# Anand1-BottomNew.net
KiCad netlist of a schematic drawn in EAGLE
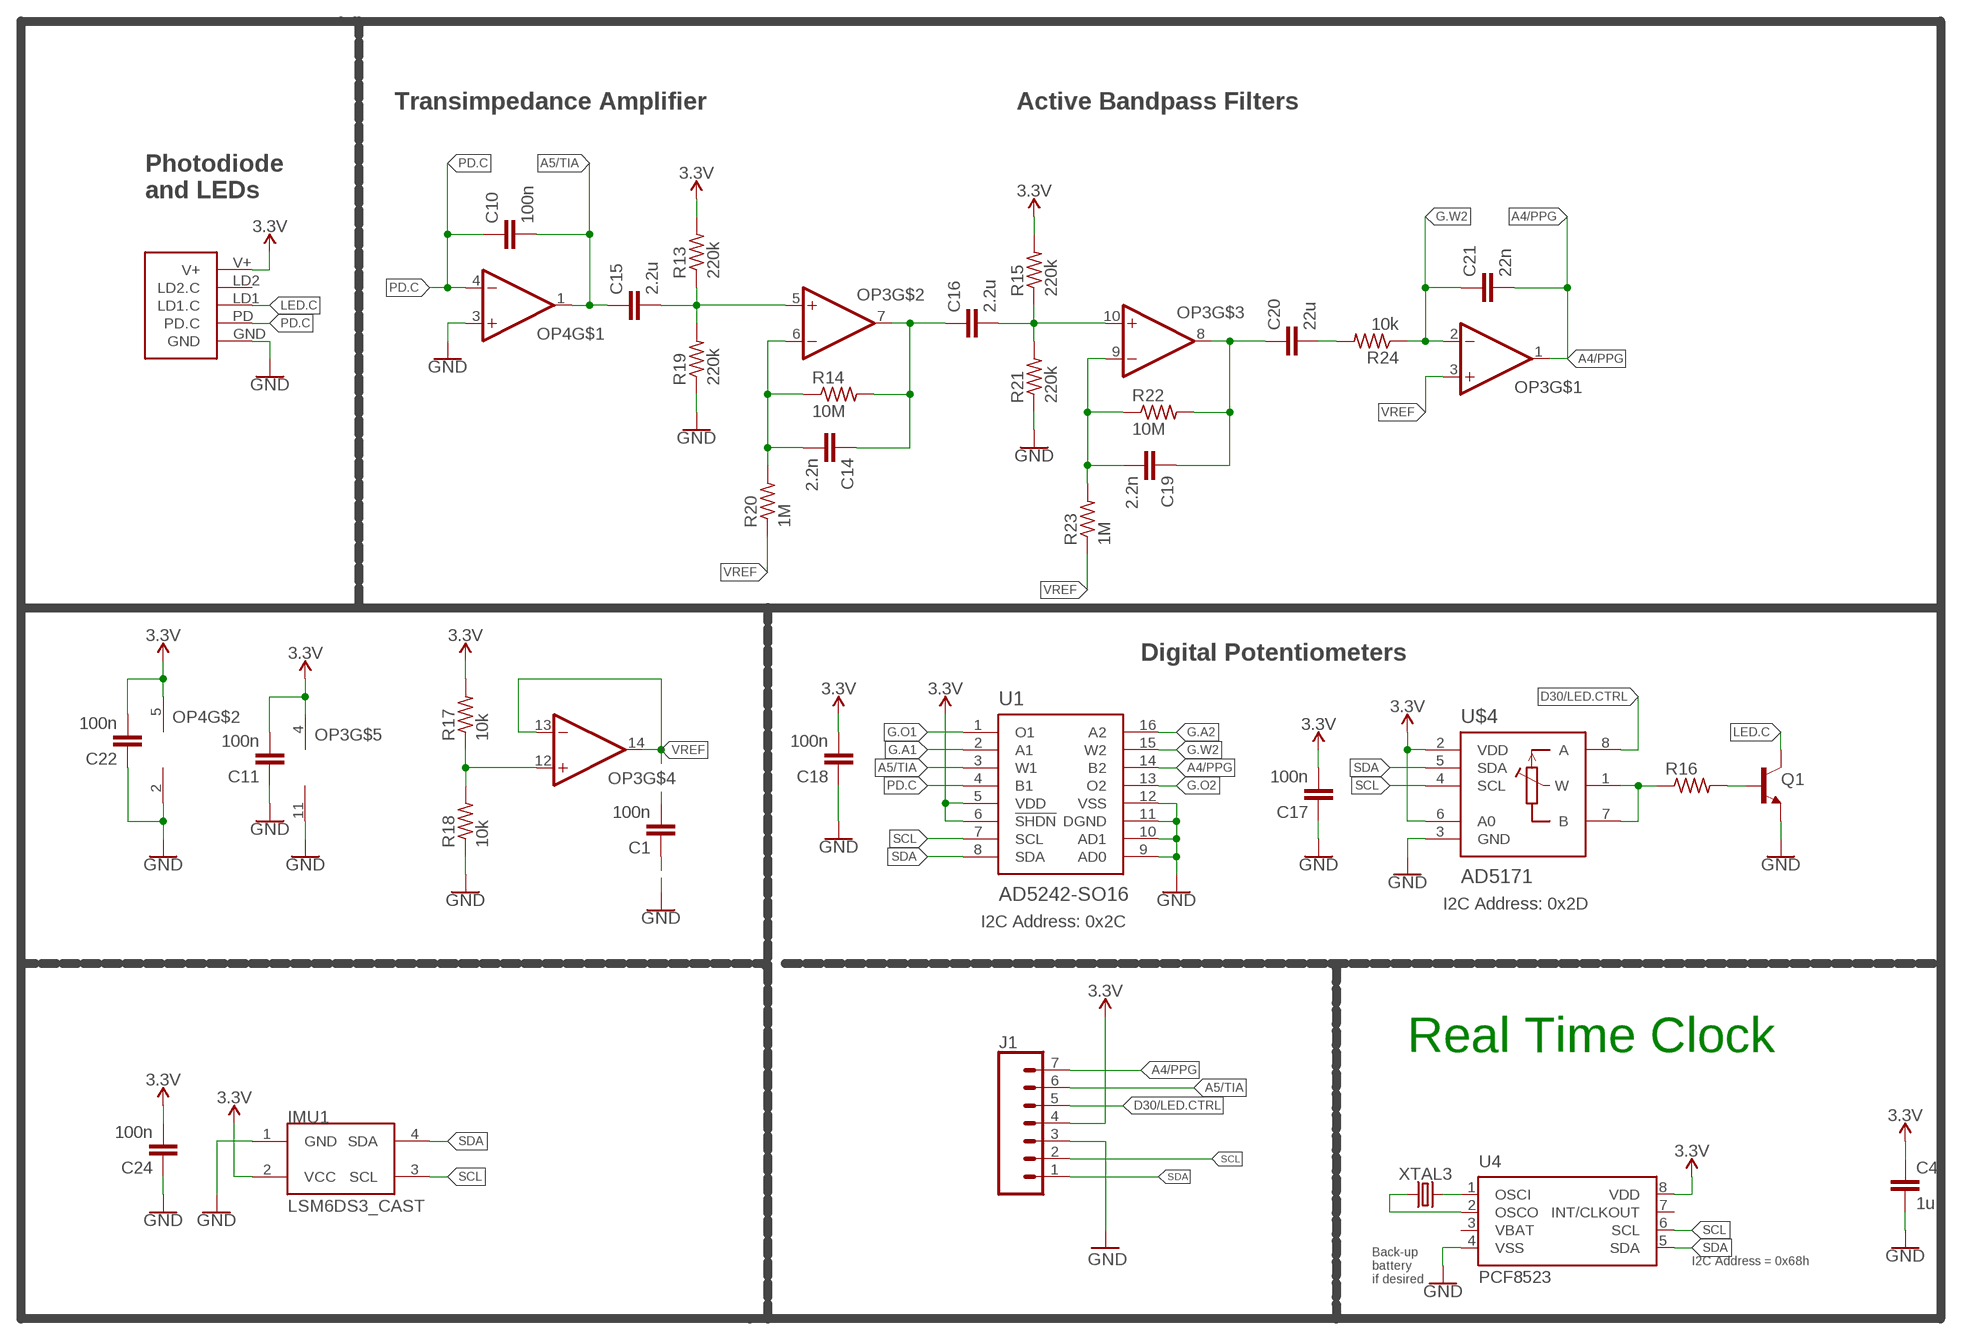
[diagram p0: schematic, sheet 1]

(export (version "E")
  (design (tool "Eeschema 10.0.6"))
  (components
    (comp (ref "C1")
      (value "100n")
      (footprint "eagle-import:C0603")
      (libsource (lib "eagle-import") (part "CAPACITOR0603"))
    )
    (comp (ref "C4")
      (value "1u")
      (footprint "eagle-import:C0603")
      (libsource (lib "eagle-import") (part "CAPACITOR0603"))
    )
    (comp (ref "C10")
      (value "100n")
      (footprint "eagle-import:C0603")
      (libsource (lib "eagle-import") (part "CAPACITOR0603"))
    )
    (comp (ref "C11")
      (value "100n")
      (footprint "eagle-import:C0603")
      (libsource (lib "eagle-import") (part "CAPACITOR0603"))
    )
    (comp (ref "C14")
      (value "2.2n")
      (footprint "eagle-import:C0603")
      (libsource (lib "eagle-import") (part "CAPACITOR0603"))
    )
    (comp (ref "C15")
      (value "2.2u")
      (footprint "eagle-import:C0603")
      (libsource (lib "eagle-import") (part "CAPACITOR0603"))
    )
    (comp (ref "C16")
      (value "2.2u")
      (footprint "eagle-import:C0603")
      (libsource (lib "eagle-import") (part "CAPACITOR0603"))
    )
    (comp (ref "C17")
      (value "100n")
      (footprint "eagle-import:C0603")
      (libsource (lib "eagle-import") (part "CAPACITOR0603"))
    )
    (comp (ref "C18")
      (value "100n")
      (footprint "eagle-import:C0603")
      (libsource (lib "eagle-import") (part "CAPACITOR0603"))
    )
    (comp (ref "C19")
      (value "2.2n")
      (footprint "eagle-import:C0603")
      (libsource (lib "eagle-import") (part "CAPACITOR0603"))
    )
    (comp (ref "C20")
      (value "22u")
      (footprint "eagle-import:C0603")
      (libsource (lib "eagle-import") (part "CAPACITOR0603"))
    )
    (comp (ref "C21")
      (value "22n")
      (footprint "eagle-import:C0603")
      (libsource (lib "eagle-import") (part "CAPACITOR0603"))
    )
    (comp (ref "C22")
      (value "100n")
      (footprint "eagle-import:C0603")
      (libsource (lib "eagle-import") (part "CAPACITOR0603"))
    )
    (comp (ref "C24")
      (value "100n")
      (footprint "eagle-import:C0603")
      (libsource (lib "eagle-import") (part "CAPACITOR0603"))
    )
    (comp (ref "IMU1")
      (value "LSM6DS3_CAST")
      (footprint "eagle-import:LSM6DS3_CAST")
      (libsource (lib "eagle-import") (part "LSM6DS3_CAST"))
    )
    (comp (ref "J1")
      (value "CONN_07-1.27MM")
      (footprint "eagle-import:1X07_1.27MM")
      (libsource (lib "eagle-import") (part "CONN_07-1.27MM"))
    )
    (comp (ref "OP3")
      (value "OP-QUAD-SO14")
      (footprint "eagle-import:SO14")
      (libsource (lib "eagle-import") (part "OP-QUAD-SO14"))
    )
    (comp (ref "OP4")
      (value "OP-SINGLEOT")
      (footprint "eagle-import:SOT23-5")
      (libsource (lib "eagle-import") (part "OP-SINGLEOT"))
    )
    (comp (ref "Q1")
      (value "NPN-GENERIC")
      (footprint "eagle-import:SOT23-3")
      (libsource (lib "eagle-import") (part "NPN-GENERIC"))
    )
    (comp (ref "R13")
      (value "220k")
      (footprint "eagle-import:R0603")
      (libsource (lib "eagle-import") (part "RESISTOR0603"))
    )
    (comp (ref "R14")
      (value "10M")
      (footprint "eagle-import:R0603")
      (libsource (lib "eagle-import") (part "RESISTOR0603"))
    )
    (comp (ref "R15")
      (value "220k")
      (footprint "eagle-import:R0603")
      (libsource (lib "eagle-import") (part "RESISTOR0603"))
    )
    (comp (ref "R16")
      (value "RESISTOR0603")
      (footprint "eagle-import:R0603")
      (libsource (lib "eagle-import") (part "RESISTOR0603"))
    )
    (comp (ref "R17")
      (value "10k")
      (footprint "eagle-import:R0402")
      (libsource (lib "eagle-import") (part "RESISTOR0402"))
    )
    (comp (ref "R18")
      (value "10k")
      (footprint "eagle-import:R0402")
      (libsource (lib "eagle-import") (part "RESISTOR0402"))
    )
    (comp (ref "R19")
      (value "220k")
      (footprint "eagle-import:R0603")
      (libsource (lib "eagle-import") (part "RESISTOR0603"))
    )
    (comp (ref "R20")
      (value "1M")
      (footprint "eagle-import:R0603")
      (libsource (lib "eagle-import") (part "RESISTOR0603"))
    )
    (comp (ref "R21")
      (value "220k")
      (footprint "eagle-import:R0603")
      (libsource (lib "eagle-import") (part "RESISTOR0603"))
    )
    (comp (ref "R22")
      (value "10M")
      (footprint "eagle-import:R0603")
      (libsource (lib "eagle-import") (part "RESISTOR0603"))
    )
    (comp (ref "R23")
      (value "1M")
      (footprint "eagle-import:R0603")
      (libsource (lib "eagle-import") (part "RESISTOR0603"))
    )
    (comp (ref "R24")
      (value "10k")
      (footprint "eagle-import:R0603")
      (libsource (lib "eagle-import") (part "RESISTOR0603"))
    )
    (comp (ref "U$3")
      (value "PPG.MODULE.2")
      (footprint "eagle-import:PPG.MODULE.2")
      (libsource (lib "eagle-import") (part "PPG.MODULE.2"))
    )
    (comp (ref "U$4")
      (value "AD5171")
      (footprint "eagle-import:SOT-23-8")
      (libsource (lib "eagle-import") (part "AD5171"))
    )
    (comp (ref "U1")
      (value "AD5242-SO16")
      (footprint "eagle-import:SO16")
      (libsource (lib "eagle-import") (part "AD5242-SO16"))
    )
    (comp (ref "U4")
      (value "PCF8523")
      (footprint "eagle-import:SO8")
      (libsource (lib "eagle-import") (part "PCF8523"))
    )
    (comp (ref "XTAL3")
      (value "32.7680kHz")
      (footprint "eagle-import:2-SMD.NOLEAD.2.0MMTO1.2MM")
      (libsource (lib "eagle-import") (part "CRYSTALECS-.327-12.5-12-C-TR"))
    )
  )
  (nets
    (net (code "1") (name "/VBAT") (class "Default")
      (node (ref "U4") (pin "3") (pinfunction "VBAT_3") (pintype "power_in"))
    )
    (net (code "2") (name "3.3V") (class "Default")
      (node (ref "C11") (pin "2") (pinfunction "2_2") (pintype "passive"))
      (node (ref "C17") (pin "2") (pinfunction "2_2") (pintype "passive"))
      (node (ref "C18") (pin "2") (pinfunction "2_2") (pintype "passive"))
      (node (ref "C22") (pin "2") (pinfunction "2_2") (pintype "passive"))
      (node (ref "C24") (pin "2") (pinfunction "2_2") (pintype "passive"))
      (node (ref "C4") (pin "1") (pinfunction "1_1") (pintype "passive"))
      (node (ref "IMU1") (pin "2") (pinfunction "VCC_2") (pintype "bidirectional"))
      (node (ref "J1") (pin "4") (pinfunction "4_4") (pintype "passive"))
      (node (ref "OP3") (pin "4") (pinfunction "V+_4") (pintype "power_in"))
      (node (ref "OP4") (pin "5") (pinfunction "V+_5") (pintype "power_in"))
      (node (ref "R13") (pin "2") (pinfunction "2_2") (pintype "passive"))
      (node (ref "R15") (pin "2") (pinfunction "2_2") (pintype "passive"))
      (node (ref "R17") (pin "2") (pinfunction "2_2") (pintype "passive"))
      (node (ref "U$3") (pin "V+") (pinfunction "V+_V+") (pintype "bidirectional"))
      (node (ref "U$4") (pin "2") (pinfunction "VDD_2") (pintype "bidirectional"))
      (node (ref "U$4") (pin "6") (pinfunction "A0_6") (pintype "bidirectional"))
      (node (ref "U1") (pin "5") (pinfunction "VDD_5") (pintype "bidirectional"))
      (node (ref "U1") (pin "6") (pinfunction "~{SHDN}_6") (pintype "bidirectional"))
      (node (ref "U4") (pin "8") (pinfunction "VDD_8") (pintype "power_in"))
    )
    (net (code "3") (name "A4{slash}PPG") (class "Default")
      (node (ref "C21") (pin "2") (pinfunction "2_2") (pintype "passive"))
      (node (ref "J1") (pin "7") (pinfunction "7_7") (pintype "passive"))
      (node (ref "OP3") (pin "1") (pinfunction "OUT_1") (pintype "output"))
      (node (ref "U1") (pin "14") (pinfunction "B2_14") (pintype "bidirectional"))
    )
    (net (code "4") (name "A5{slash}TIA") (class "Default")
      (node (ref "C10") (pin "2") (pinfunction "2_2") (pintype "passive"))
      (node (ref "C15") (pin "1") (pinfunction "1_1") (pintype "passive"))
      (node (ref "J1") (pin "6") (pinfunction "6_6") (pintype "passive"))
      (node (ref "OP4") (pin "1") (pinfunction "OUT_1") (pintype "output"))
      (node (ref "U1") (pin "3") (pinfunction "W1_3") (pintype "bidirectional"))
    )
    (net (code "5") (name "D30{slash}LED.CTRL") (class "Default")
      (node (ref "J1") (pin "5") (pinfunction "5_5") (pintype "passive"))
      (node (ref "U$4") (pin "8") (pinfunction "A_8") (pintype "bidirectional"))
    )
    (net (code "6") (name "G.A1") (class "Default")
      (node (ref "U1") (pin "2") (pinfunction "A1_2") (pintype "bidirectional"))
    )
    (net (code "7") (name "G.A2") (class "Default")
      (node (ref "U1") (pin "16") (pinfunction "A2_16") (pintype "bidirectional"))
    )
    (net (code "8") (name "G.O1") (class "Default")
      (node (ref "U1") (pin "1") (pinfunction "O1_1") (pintype "bidirectional"))
    )
    (net (code "9") (name "G.O2") (class "Default")
      (node (ref "U1") (pin "13") (pinfunction "O2_13") (pintype "bidirectional"))
    )
    (net (code "10") (name "G.W2") (class "Default")
      (node (ref "C21") (pin "1") (pinfunction "1_1") (pintype "passive"))
      (node (ref "OP3") (pin "2") (pinfunction "-IN_2") (pintype "input"))
      (node (ref "R24") (pin "1") (pinfunction "1_1") (pintype "passive"))
      (node (ref "U1") (pin "15") (pinfunction "W2_15") (pintype "bidirectional"))
    )
    (net (code "11") (name "GND") (class "Default")
      (node (ref "C1") (pin "1") (pinfunction "1_1") (pintype "passive"))
      (node (ref "C11") (pin "1") (pinfunction "1_1") (pintype "passive"))
      (node (ref "C17") (pin "1") (pinfunction "1_1") (pintype "passive"))
      (node (ref "C18") (pin "1") (pinfunction "1_1") (pintype "passive"))
      (node (ref "C22") (pin "1") (pinfunction "1_1") (pintype "passive"))
      (node (ref "C24") (pin "1") (pinfunction "1_1") (pintype "passive"))
      (node (ref "C4") (pin "2") (pinfunction "2_2") (pintype "passive"))
      (node (ref "IMU1") (pin "1") (pinfunction "GND_1") (pintype "bidirectional"))
      (node (ref "J1") (pin "3") (pinfunction "3_3") (pintype "passive"))
      (node (ref "OP3") (pin "11") (pinfunction "V-_11") (pintype "power_in"))
      (node (ref "OP4") (pin "2") (pinfunction "V-_2") (pintype "power_in"))
      (node (ref "OP4") (pin "3") (pinfunction "+IN_3") (pintype "input"))
      (node (ref "Q1") (pin "2") (pinfunction "E_2") (pintype "passive"))
      (node (ref "R18") (pin "1") (pinfunction "1_1") (pintype "passive"))
      (node (ref "R19") (pin "1") (pinfunction "1_1") (pintype "passive"))
      (node (ref "R21") (pin "1") (pinfunction "1_1") (pintype "passive"))
      (node (ref "U$3") (pin "GND") (pinfunction "GND_GND") (pintype "bidirectional"))
      (node (ref "U$4") (pin "3") (pinfunction "GND_3") (pintype "bidirectional"))
      (node (ref "U1") (pin "10") (pinfunction "AD1_10") (pintype "bidirectional"))
      (node (ref "U1") (pin "11") (pinfunction "DGND_11") (pintype "bidirectional"))
      (node (ref "U1") (pin "12") (pinfunction "VSS_12") (pintype "bidirectional"))
      (node (ref "U1") (pin "9") (pinfunction "AD0_9") (pintype "bidirectional"))
      (node (ref "U4") (pin "4") (pinfunction "VSS_4") (pintype "power_in"))
    )
    (net (code "12") (name "LED.C") (class "Default")
      (node (ref "Q1") (pin "3") (pinfunction "C_3") (pintype "passive"))
      (node (ref "U$3") (pin "LD1") (pinfunction "LD1.C_LD1") (pintype "bidirectional"))
    )
    (net (code "13") (name "Net-(C20-Pad2)") (class "Default")
      (node (ref "C20") (pin "2") (pinfunction "2_2") (pintype "passive"))
      (node (ref "R24") (pin "2") (pinfunction "2_2") (pintype "passive"))
    )
    (net (code "14") (name "Net-(OP3B-+IN)") (class "Default")
      (node (ref "C15") (pin "2") (pinfunction "2_2") (pintype "passive"))
      (node (ref "OP3") (pin "5") (pinfunction "+IN_5") (pintype "input"))
      (node (ref "R13") (pin "1") (pinfunction "1_1") (pintype "passive"))
      (node (ref "R19") (pin "2") (pinfunction "2_2") (pintype "passive"))
    )
    (net (code "15") (name "Net-(OP3B--IN)") (class "Default")
      (node (ref "C14") (pin "2") (pinfunction "2_2") (pintype "passive"))
      (node (ref "OP3") (pin "6") (pinfunction "-IN_6") (pintype "input"))
      (node (ref "R14") (pin "1") (pinfunction "1_1") (pintype "passive"))
      (node (ref "R20") (pin "2") (pinfunction "2_2") (pintype "passive"))
    )
    (net (code "16") (name "Net-(OP3B-OUT)") (class "Default")
      (node (ref "C14") (pin "1") (pinfunction "1_1") (pintype "passive"))
      (node (ref "C16") (pin "1") (pinfunction "1_1") (pintype "passive"))
      (node (ref "OP3") (pin "7") (pinfunction "OUT_7") (pintype "output"))
      (node (ref "R14") (pin "2") (pinfunction "2_2") (pintype "passive"))
    )
    (net (code "17") (name "Net-(OP3C-+IN)") (class "Default")
      (node (ref "C16") (pin "2") (pinfunction "2_2") (pintype "passive"))
      (node (ref "OP3") (pin "10") (pinfunction "+IN_10") (pintype "input"))
      (node (ref "R15") (pin "1") (pinfunction "1_1") (pintype "passive"))
      (node (ref "R21") (pin "2") (pinfunction "2_2") (pintype "passive"))
    )
    (net (code "18") (name "Net-(OP3C--IN)") (class "Default")
      (node (ref "C19") (pin "2") (pinfunction "2_2") (pintype "passive"))
      (node (ref "OP3") (pin "9") (pinfunction "-IN_9") (pintype "input"))
      (node (ref "R22") (pin "1") (pinfunction "1_1") (pintype "passive"))
      (node (ref "R23") (pin "2") (pinfunction "2_2") (pintype "passive"))
    )
    (net (code "19") (name "Net-(OP3C-OUT)") (class "Default")
      (node (ref "C19") (pin "1") (pinfunction "1_1") (pintype "passive"))
      (node (ref "C20") (pin "1") (pinfunction "1_1") (pintype "passive"))
      (node (ref "OP3") (pin "8") (pinfunction "OUT_8") (pintype "output"))
      (node (ref "R22") (pin "2") (pinfunction "2_2") (pintype "passive"))
    )
    (net (code "20") (name "Net-(OP3D-+IN)") (class "Default")
      (node (ref "OP3") (pin "12") (pinfunction "+IN_12") (pintype "input"))
      (node (ref "R17") (pin "1") (pinfunction "1_1") (pintype "passive"))
      (node (ref "R18") (pin "2") (pinfunction "2_2") (pintype "passive"))
    )
    (net (code "21") (name "Net-(Q1-B)") (class "Default")
      (node (ref "Q1") (pin "1") (pinfunction "B_1") (pintype "passive"))
      (node (ref "R16") (pin "2") (pinfunction "2_2") (pintype "passive"))
    )
    (net (code "22") (name "Net-(U$4-B)") (class "Default")
      (node (ref "R16") (pin "1") (pinfunction "1_1") (pintype "passive"))
      (node (ref "U$4") (pin "1") (pinfunction "W_1") (pintype "bidirectional"))
      (node (ref "U$4") (pin "7") (pinfunction "B_7") (pintype "bidirectional"))
    )
    (net (code "23") (name "Net-(U4-OSCI)") (class "Default")
      (node (ref "U4") (pin "1") (pinfunction "OSCI_1") (pintype "bidirectional"))
      (node (ref "XTAL3") (pin "P$2") (pinfunction "2_P$2") (pintype "passive"))
    )
    (net (code "24") (name "Net-(U4-OSCO)") (class "Default")
      (node (ref "U4") (pin "2") (pinfunction "OSCO_2") (pintype "bidirectional"))
      (node (ref "XTAL3") (pin "P$1") (pinfunction "1_P$1") (pintype "passive"))
    )
    (net (code "25") (name "PD.C") (class "Default")
      (node (ref "C10") (pin "1") (pinfunction "1_1") (pintype "passive"))
      (node (ref "OP4") (pin "4") (pinfunction "-IN_4") (pintype "input"))
      (node (ref "U$3") (pin "PD") (pinfunction "PD.C_PD") (pintype "bidirectional"))
      (node (ref "U1") (pin "4") (pinfunction "B1_4") (pintype "bidirectional"))
    )
    (net (code "26") (name "SCL") (class "Default")
      (node (ref "IMU1") (pin "3") (pinfunction "SCL_3") (pintype "bidirectional"))
      (node (ref "J1") (pin "2") (pinfunction "2_2") (pintype "passive"))
      (node (ref "U$4") (pin "4") (pinfunction "SCL_4") (pintype "bidirectional"))
      (node (ref "U1") (pin "7") (pinfunction "SCL_7") (pintype "bidirectional"))
      (node (ref "U4") (pin "6") (pinfunction "SCL_6") (pintype "bidirectional"))
    )
    (net (code "27") (name "SDA") (class "Default")
      (node (ref "IMU1") (pin "4") (pinfunction "SDA_4") (pintype "bidirectional"))
      (node (ref "J1") (pin "1") (pinfunction "1_1") (pintype "passive"))
      (node (ref "U$4") (pin "5") (pinfunction "SDA_5") (pintype "bidirectional"))
      (node (ref "U1") (pin "8") (pinfunction "SDA_8") (pintype "bidirectional"))
      (node (ref "U4") (pin "5") (pinfunction "SDA_5") (pintype "bidirectional"))
    )
    (net (code "28") (name "VREF") (class "Default")
      (node (ref "C1") (pin "2") (pinfunction "2_2") (pintype "passive"))
      (node (ref "OP3") (pin "13") (pinfunction "-IN_13") (pintype "input"))
      (node (ref "OP3") (pin "14") (pinfunction "OUT_14") (pintype "output"))
      (node (ref "OP3") (pin "3") (pinfunction "+IN_3") (pintype "input"))
      (node (ref "R20") (pin "1") (pinfunction "1_1") (pintype "passive"))
      (node (ref "R23") (pin "1") (pinfunction "1_1") (pintype "passive"))
    )
    (net (code "29") (name "unconnected-(U$3-LD2.C-PadLD2)") (class "Default")
      (node (ref "U$3") (pin "LD2") (pinfunction "LD2.C_LD2") (pintype "bidirectional"))
    )
    (net (code "30") (name "unconnected-(U4-INT{slash}CLKOUT-Pad7)") (class "Default")
      (node (ref "U4") (pin "7") (pinfunction "INT/CLKOUT_7") (pintype "bidirectional"))
    )
  )
)
